# design.net
KiCad netlist of a schematic drawn in EasyEDA Pro
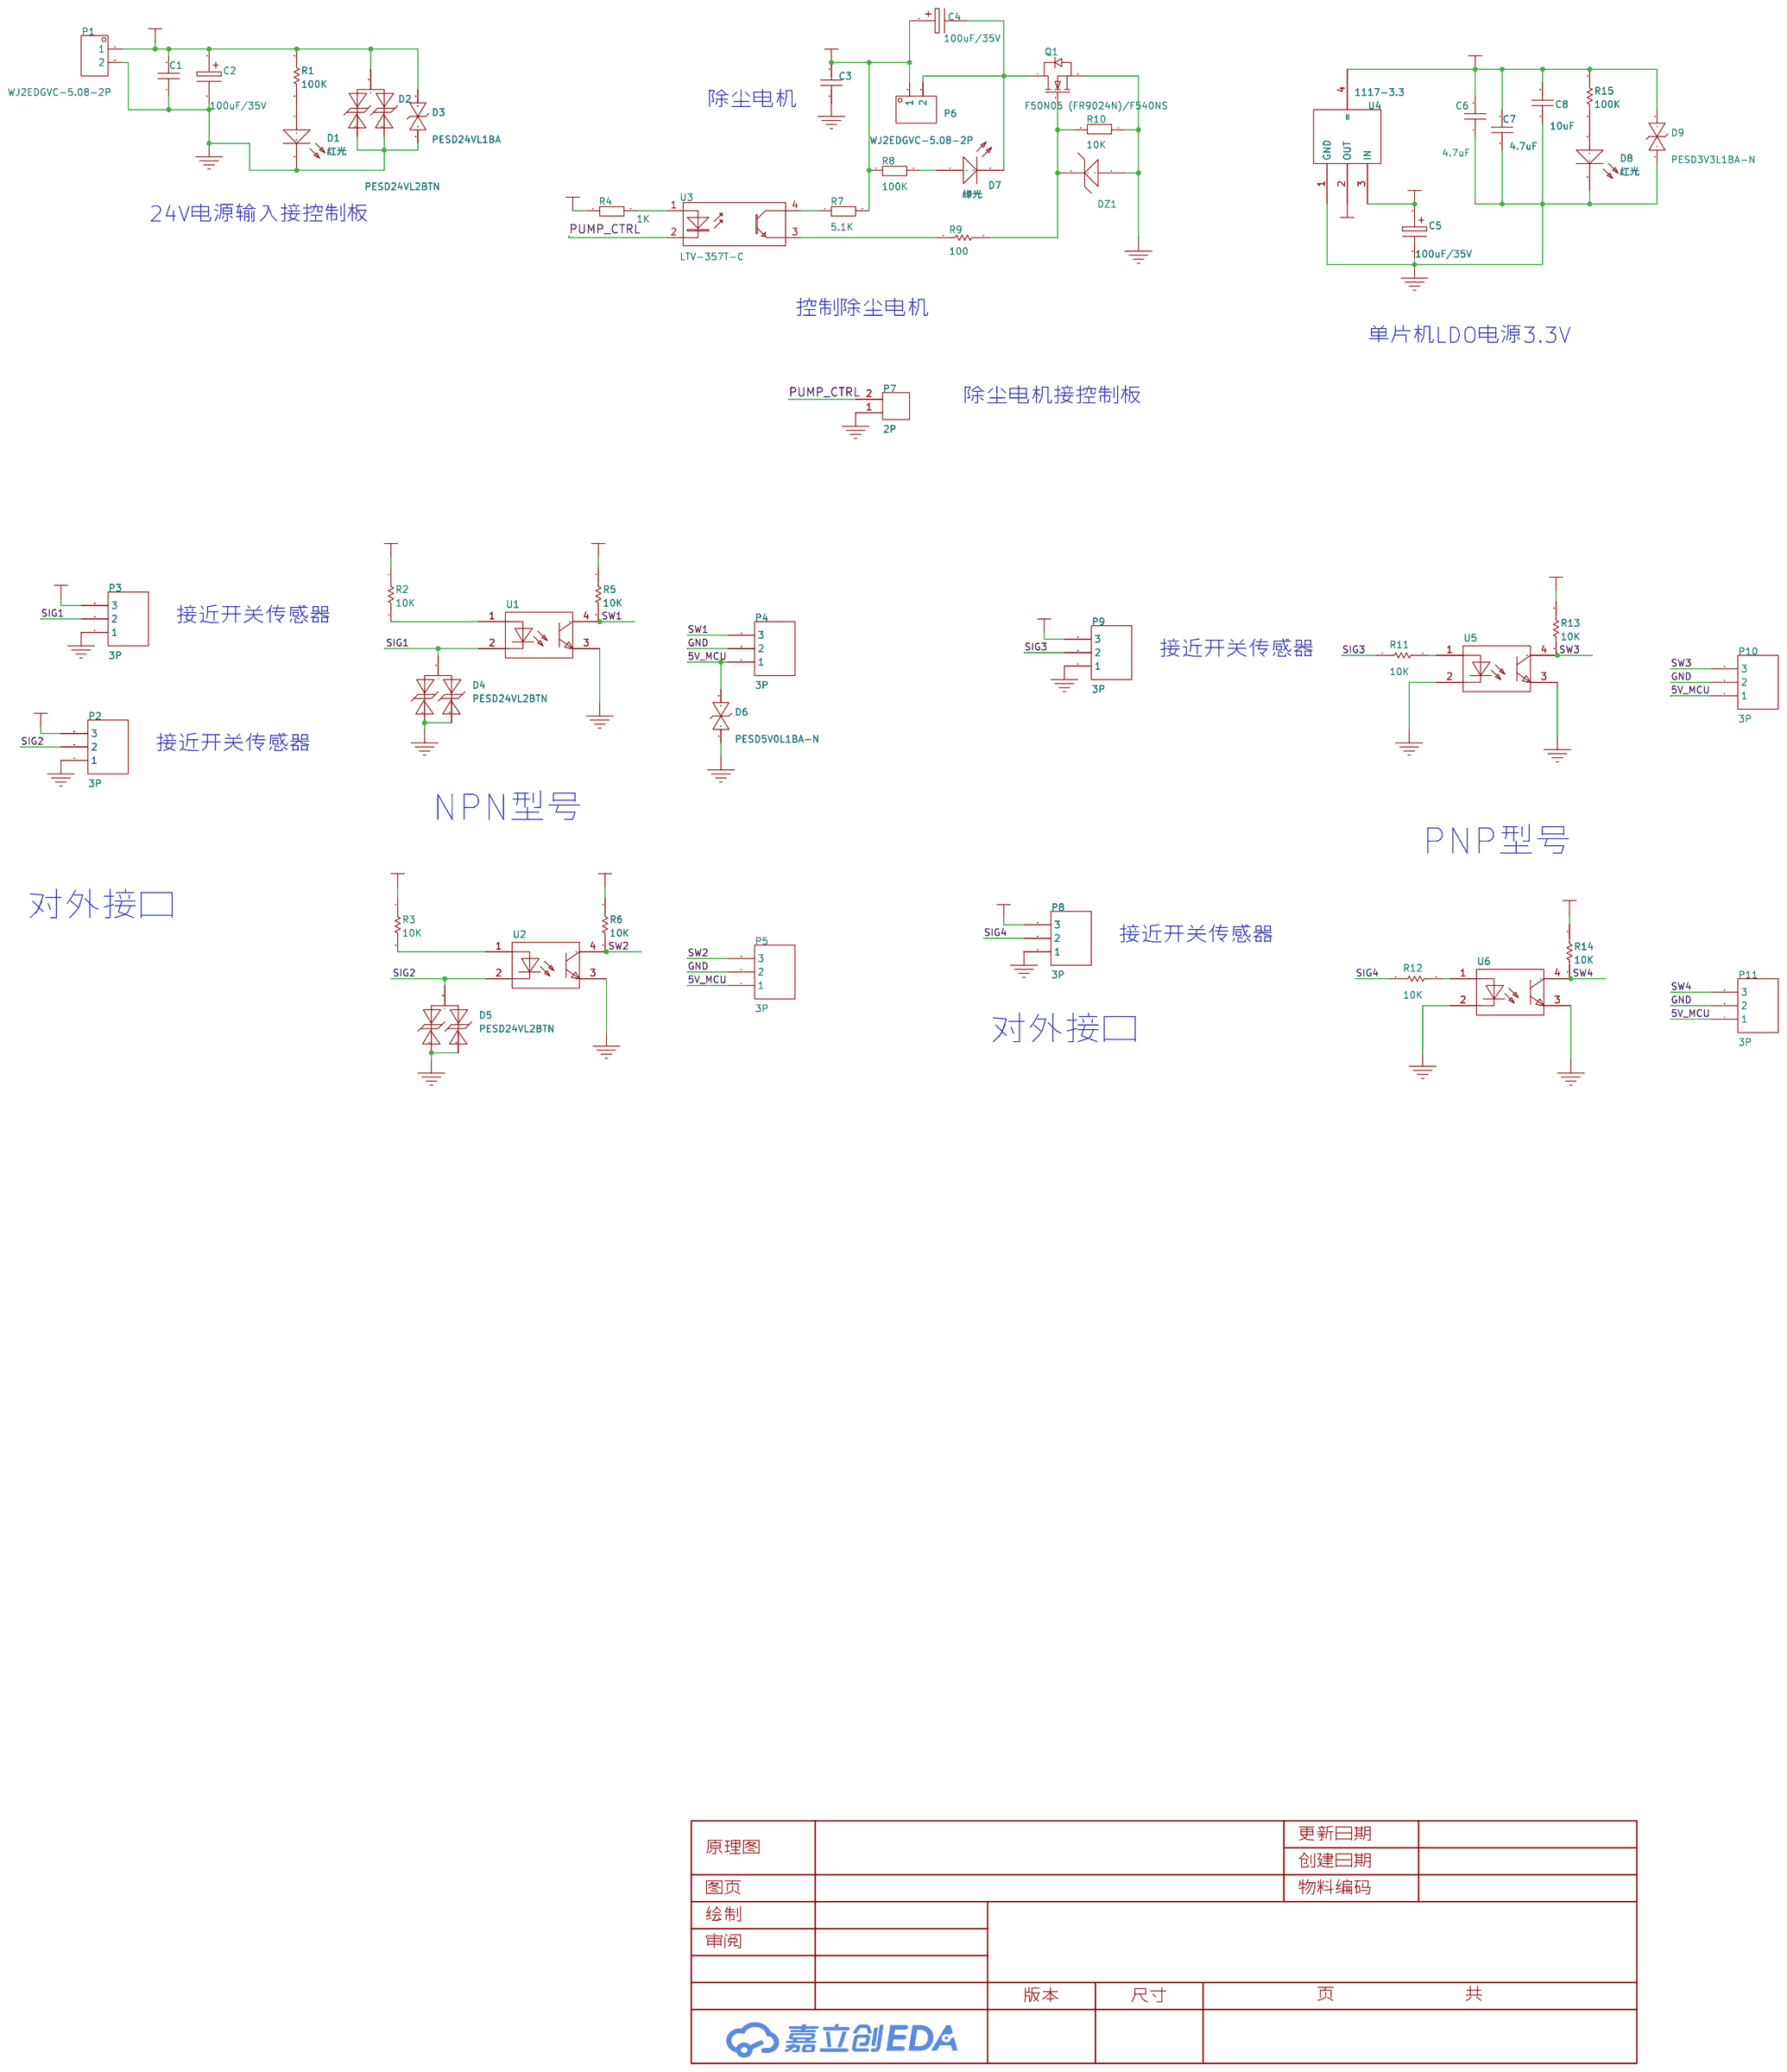
[diagram p0: 主控MCU]
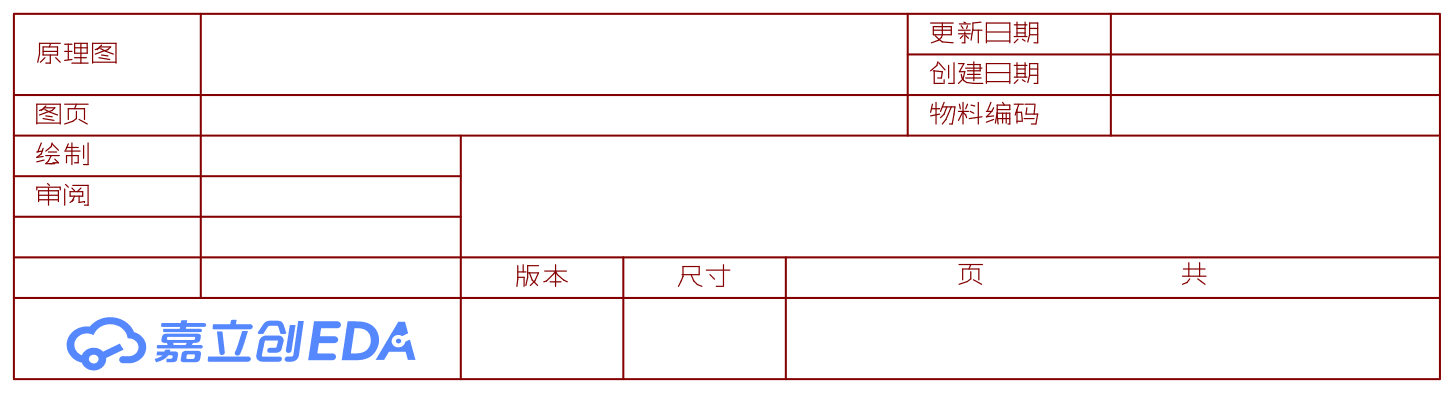
[diagram p1: 电源及控制]

(export (version "E")
  (design (tool "Eeschema 10.0.6"))
  (components
    (comp (ref "C1")
      (value "104")
      (footprint "easyedapro:电解电容贴片6x6")
      (libsource (lib "easyedapro") (part "CAP"))
    )
    (comp (ref "C2") (value "100uF/35V") (libsource (lib "") (part "ELECTRO1_1")))
    (comp (ref "C3")
      (value "104")
      (footprint "easyedapro:电解电容贴片6x6")
      (libsource (lib "easyedapro") (part "CAP"))
    )
    (comp (ref "C4")
      (value "100uF/35V")
      (footprint "easyedapro:0603C")
      (libsource (lib "easyedapro") (part "ELECTRO1"))
    )
    (comp (ref "C5")
      (value "100uF/35V")
      (footprint "easyedapro:电解电容贴片10x10")
      (libsource (lib "easyedapro") (part "ELECTRO1"))
    )
    (comp (ref "C6")
      (value "4.7uF")
      (footprint "easyedapro:C1206")
      (description "容值:4.7uF;精度:±10%;额定电压:50V;材质(温度系数):X7R;")
      (fields (field (name "Manufacturer Part") "1206B475K500NT") (field (name "Manufacturer") "FH(风华)"))
      (libsource (lib "easyedapro") (part "1206B475K500NT"))
    )
    (comp (ref "C7")
      (value "4.7uF")
      (footprint "easyedapro:C1206")
      (description "容值:4.7uF;精度:±10%;额定电压:50V;材质(温度系数):X7R;")
      (fields (field (name "Manufacturer Part") "1206B475K500NT") (field (name "Manufacturer") "FH(风华)"))
      (libsource (lib "easyedapro") (part "1206B475K500NT"))
    )
    (comp (ref "C8")
      (value "10uF")
      (footprint "easyedapro:0603C")
      (description "Capacitor (Semiconductor SIM Model)")
      (libsource (lib "easyedapro") (part "Cap Semi"))
    )
    (comp (ref "D1")
      (value "红光")
      (footprint "easyedapro:0603LED")
      (libsource (lib "easyedapro") (part "LED"))
    )
    (comp (ref "D2")
      (value "PESD24VL2BTN")
      (footprint "easyedapro:SOT-23-3_L2.9-W1.6-P1.90-LS2.8-BR")
      (description "极性:Bidirectional;反向关断电压（典型值）:24V (Max);击穿电压（最小值）:26.7V;箝位电压:48V;峰值脉冲电流（10/1000us）:6A (8/20us);")
      (fields (field (name "Manufacturer") "BORN伯恩半导体"))
      (libsource (lib "easyedapro") (part "PESD24VL2BTN"))
    )
    (comp (ref "D3")
      (value "PESD24VL1BA")
      (footprint "easyedapro:SOD-323_L1.7-W1.3-LS2.5-BI")
      (description "极性:双向;反向截止电压(Vrwm):3.3V;最大钳位电压:16V;击穿电压:4V;")
      (fields (field (name "Manufacturer") "TECH PUBLIC(台舟)"))
      (libsource (lib "easyedapro") (part "pesd03v32d-lc"))
    )
    (comp (ref "D4")
      (value "PESD24VL2BTN")
      (footprint "easyedapro:SOT-23-3_L2.9-W1.6-P1.90-LS2.8-BR")
      (description "极性:Bidirectional;反向关断电压（典型值）:24V (Max);击穿电压（最小值）:26.7V;箝位电压:48V;峰值脉冲电流（10/1000us）:6A (8/20us);")
      (fields (field (name "Manufacturer") "BORN伯恩半导体"))
      (libsource (lib "easyedapro") (part "PESD24VL2BTN"))
    )
    (comp (ref "D5")
      (value "PESD24VL2BTN")
      (footprint "easyedapro:SOT-23-3_L2.9-W1.6-P1.90-LS2.8-BR")
      (description "极性:Bidirectional;反向关断电压（典型值）:24V (Max);击穿电压（最小值）:26.7V;箝位电压:48V;峰值脉冲电流（10/1000us）:6A (8/20us);")
      (fields (field (name "Manufacturer") "BORN伯恩半导体"))
      (libsource (lib "easyedapro") (part "PESD24VL2BTN"))
    )
    (comp (ref "D6")
      (value "PESD5V0L1BA-N")
      (footprint "easyedapro:SOD-323_L1.7-W1.3-LS2.5-BI")
      (description "极性:双向;反向截止电压(Vrwm):3.3V;最大钳位电压:16V;击穿电压:4V;")
      (fields (field (name "Manufacturer") "TECH PUBLIC(台舟)"))
      (libsource (lib "easyedapro") (part "pesd03v32d-lc"))
    )
    (comp (ref "D7") (value "绿光") (footprint "easyedapro:SMA") (libsource (lib "easyedapro") (part "LED")))
    (comp (ref "D8")
      (value "红光")
      (footprint "easyedapro:0603LED")
      (libsource (lib "easyedapro") (part "LED"))
    )
    (comp (ref "D9")
      (value "PESD3V3L1BA-N")
      (footprint "easyedapro:SOD-323_L1.7-W1.3-LS2.5-BI")
      (description "极性:双向;反向截止电压(Vrwm):3.3V;最大钳位电压:16V;击穿电压:4V;")
      (fields (field (name "Manufacturer") "TECH PUBLIC(台舟)"))
      (libsource (lib "easyedapro") (part "pesd03v32d-lc"))
    )
    (comp (ref "DZ1") (value "--ѹ------SMAZ10V") (libsource (lib "easyedapro") (part "ѹ")))
    (comp (ref "P1")
      (value "WJ2EDGVC-5.08-2P")
      (footprint "easyedapro:CONN-TH_WJ2EDGVC-5.08-2P")
      (fields (field (name "Manufacturer") "KANGNEX(康奈克斯电气)"))
      (libsource (lib "easyedapro") (part "WJ2EDGVC-5.08-2P"))
    )
    (comp (ref "P2")
      (value "3P")
      (footprint "easyedapro:HDR1X3_CON")
      (libsource (lib "easyedapro") (part "3P"))
    )
    (comp (ref "P3")
      (value "3P")
      (footprint "easyedapro:HDR1X3_CON")
      (libsource (lib "easyedapro") (part "3P"))
    )
    (comp (ref "P4")
      (value "3P")
      (footprint "easyedapro:HDR1X3_CON")
      (libsource (lib "easyedapro") (part "3P"))
    )
    (comp (ref "P5")
      (value "3P")
      (footprint "easyedapro:HDR1X3_CON")
      (libsource (lib "easyedapro") (part "3P"))
    )
    (comp (ref "P6")
      (value "WJ2EDGVC-5.08-2P")
      (footprint "easyedapro:CONN-TH_WJ2EDGVC-5.08-2P")
      (fields (field (name "Manufacturer") "KANGNEX(康奈克斯电气)"))
      (libsource (lib "easyedapro") (part "WJ2EDGVC-5.08-2P"))
    )
    (comp (ref "P7") (value "2P") (libsource (lib "easyedapro") (part "2P")))
    (comp (ref "P8")
      (value "3P")
      (footprint "easyedapro:HDR1X3_CON")
      (libsource (lib "easyedapro") (part "3P"))
    )
    (comp (ref "P9")
      (value "3P")
      (footprint "easyedapro:HDR1X3_CON")
      (libsource (lib "easyedapro") (part "3P"))
    )
    (comp (ref "P10")
      (value "3P")
      (footprint "easyedapro:HDR1X3_CON")
      (libsource (lib "easyedapro") (part "3P"))
    )
    (comp (ref "P11")
      (value "3P")
      (footprint "easyedapro:HDR1X3_CON")
      (libsource (lib "easyedapro") (part "3P"))
    )
    (comp (ref "Q1")
      (value "F50N06 (FR9024N)/F540NS")
      (footprint "easyedapro:TO-263-2_L10.0-W9.1-P5.08-LS15.2-TL")
      (fields (field (name "Manufacturer") "Infineon(英飞凌)"))
      (libsource (lib "easyedapro") (part "IRF540NSTRLPBF"))
    )
    (comp (ref "R1")
      (value "100K")
      (footprint "easyedapro:0603R")
      (description "Resistor")
      (libsource (lib "easyedapro") (part "RES"))
    )
    (comp (ref "R2")
      (value "10K")
      (footprint "easyedapro:0603R")
      (description "Resistor")
      (libsource (lib "easyedapro") (part "RES"))
    )
    (comp (ref "R3")
      (value "10K")
      (footprint "easyedapro:0603R")
      (description "Resistor")
      (libsource (lib "easyedapro") (part "RES"))
    )
    (comp (ref "R4") (value "1K") (footprint "easyedapro:0603R") (libsource (lib "easyedapro") (part "res")))
    (comp (ref "R5")
      (value "10K")
      (footprint "easyedapro:0603R")
      (description "Resistor")
      (libsource (lib "easyedapro") (part "RES"))
    )
    (comp (ref "R6")
      (value "10K")
      (footprint "easyedapro:0603R")
      (description "Resistor")
      (libsource (lib "easyedapro") (part "RES"))
    )
    (comp (ref "R7")
      (value "5.1K")
      (footprint "easyedapro:0603R")
      (libsource (lib "easyedapro") (part "res"))
    )
    (comp (ref "R8")
      (value "100K")
      (footprint "easyedapro:0603R")
      (libsource (lib "easyedapro") (part "res"))
    )
    (comp (ref "R9")
      (value "100")
      (footprint "easyedapro:0603R")
      (description "Resistor")
      (libsource (lib "easyedapro") (part "RES"))
    )
    (comp (ref "R10")
      (value "10K")
      (footprint "easyedapro:0603R")
      (libsource (lib "easyedapro") (part "res"))
    )
    (comp (ref "R11")
      (value "10K")
      (footprint "easyedapro:0603R")
      (description "Resistor")
      (libsource (lib "easyedapro") (part "RES"))
    )
    (comp (ref "R12")
      (value "10K")
      (footprint "easyedapro:0603R")
      (description "Resistor")
      (libsource (lib "easyedapro") (part "RES"))
    )
    (comp (ref "R13")
      (value "10K")
      (footprint "easyedapro:0603R")
      (description "Resistor")
      (libsource (lib "easyedapro") (part "RES"))
    )
    (comp (ref "R14")
      (value "10K")
      (footprint "easyedapro:0603R")
      (description "Resistor")
      (libsource (lib "easyedapro") (part "RES"))
    )
    (comp (ref "R15")
      (value "100K")
      (footprint "easyedapro:0603R")
      (description "Resistor")
      (libsource (lib "easyedapro") (part "RES"))
    )
    (comp (ref "U1")
      (value "LTV-357T-C")
      (footprint "easyedapro:SOP-4_L4.4-W3.9-P2.54-LS7.0-TL")
      (fields (field (name "Manufacturer") "LITEON(光宝)"))
      (libsource (lib "easyedapro") (part "LTV-357T-C"))
    )
    (comp (ref "U2")
      (value "LTV-357T-C")
      (footprint "easyedapro:SOP-4_L4.4-W3.9-P2.54-LS7.0-TL")
      (fields (field (name "Manufacturer") "LITEON(光宝)"))
      (libsource (lib "easyedapro") (part "LTV-357T-C"))
    )
    (comp (ref "U3")
      (value "LTV-357T-C")
      (footprint "easyedapro:SOT-23-5")
      (description "4-Pin Phototransistor Optocoupler")
      (libsource (lib "easyedapro") (part "Optoisolator1"))
    )
    (comp (ref "U4")
      (value "1117-3.3")
      (footprint "easyedapro:SOT-223")
      (libsource (lib "easyedapro") (part "LM1117"))
    )
    (comp (ref "U5")
      (value "LTV-357T-C")
      (footprint "easyedapro:SOP-4_L4.4-W3.9-P2.54-LS7.0-TL")
      (fields (field (name "Manufacturer") "LITEON(光宝)"))
      (libsource (lib "easyedapro") (part "LTV-357T-C"))
    )
    (comp (ref "U6")
      (value "LTV-357T-C")
      (footprint "easyedapro:SOP-4_L4.4-W3.9-P2.54-LS7.0-TL")
      (fields (field (name "Manufacturer") "LITEON(光宝)"))
      (libsource (lib "easyedapro") (part "LTV-357T-C"))
    )
  )
  (nets
    (net (code "1") (name "3V3") (class "Default")
      (node (ref "C6") (pin "2") (pinfunction "2_2") (pintype "input"))
      (node (ref "C7") (pin "2") (pinfunction "2_2") (pintype "input"))
      (node (ref "C8") (pin "2") (pinfunction "2_2") (pintype "unspecified"))
      (node (ref "D9") (pin "2") (pinfunction "2_2") (pintype "unspecified"))
      (node (ref "R13") (pin "1") (pinfunction "1_1") (pintype "unspecified"))
      (node (ref "R14") (pin "1") (pinfunction "1_1") (pintype "unspecified"))
      (node (ref "R15") (pin "1") (pinfunction "1_1") (pintype "unspecified"))
      (node (ref "R4") (pin "1") (pintype "unspecified"))
      (node (ref "R5") (pin "1") (pinfunction "1_1") (pintype "unspecified"))
      (node (ref "R6") (pin "1") (pinfunction "1_1") (pintype "unspecified"))
      (node (ref "U4") (pin "2") (pinfunction "OUT_2") (pintype "unspecified"))
      (node (ref "U4") (pin "4") (pinfunction "=_4") (pintype "unspecified"))
    )
    (net (code "2") (name "5V_MCU") (class "Default")
      (node (ref "C5") (pin "1") (pintype "unspecified"))
      (node (ref "D6") (pin "2") (pinfunction "2_2") (pintype "unspecified"))
      (node (ref "P10") (pin "1") (pinfunction "1_1") (pintype "unspecified"))
      (node (ref "P11") (pin "1") (pinfunction "1_1") (pintype "unspecified"))
      (node (ref "P4") (pin "1") (pinfunction "1_1") (pintype "unspecified"))
      (node (ref "P5") (pin "1") (pinfunction "1_1") (pintype "unspecified"))
      (node (ref "U4") (pin "3") (pinfunction "IN_3") (pintype "unspecified"))
    )
    (net (code "3") (name "24V") (class "Default")
      (node (ref "C1") (pin "2") (pinfunction "2_2") (pintype "unspecified"))
      (node (ref "C2") (pin "1") (pintype "input"))
      (node (ref "C3") (pin "2") (pinfunction "2_2") (pintype "unspecified"))
      (node (ref "C4") (pin "1") (pintype "unspecified"))
      (node (ref "D2") (pin "3") (pinfunction "A_3") (pintype "input"))
      (node (ref "D3") (pin "2") (pinfunction "2_2") (pintype "unspecified"))
      (node (ref "P1") (pin "1") (pinfunction "1_1") (pintype "unspecified"))
      (node (ref "P2") (pin "3") (pinfunction "3_3") (pintype "unspecified"))
      (node (ref "P3") (pin "3") (pinfunction "3_3") (pintype "unspecified"))
      (node (ref "P6") (pin "1") (pinfunction "1_1") (pintype "unspecified"))
      (node (ref "P8") (pin "3") (pinfunction "3_3") (pintype "unspecified"))
      (node (ref "P9") (pin "3") (pinfunction "3_3") (pintype "unspecified"))
      (node (ref "R1") (pin "1") (pinfunction "1_1") (pintype "unspecified"))
      (node (ref "R2") (pin "1") (pinfunction "1_1") (pintype "unspecified"))
      (node (ref "R3") (pin "1") (pinfunction "1_1") (pintype "unspecified"))
      (node (ref "R7") (pin "2") (pintype "unspecified"))
      (node (ref "R8") (pin "1") (pintype "unspecified"))
    )
    (net (code "4") (name "GND") (class "Default")
      (node (ref "C1") (pin "1") (pinfunction "1_1") (pintype "unspecified"))
      (node (ref "C2") (pin "2") (pintype "input"))
      (node (ref "C3") (pin "1") (pinfunction "1_1") (pintype "unspecified"))
      (node (ref "C5") (pin "2") (pintype "unspecified"))
      (node (ref "C6") (pin "1") (pinfunction "1_1") (pintype "input"))
      (node (ref "C7") (pin "1") (pinfunction "1_1") (pintype "input"))
      (node (ref "C8") (pin "1") (pinfunction "1_1") (pintype "unspecified"))
      (node (ref "D1") (pin "2") (pinfunction "2_2") (pintype "unspecified"))
      (node (ref "D2") (pin "1") (pinfunction "K_1") (pintype "input"))
      (node (ref "D2") (pin "2") (pinfunction "K_2") (pintype "input"))
      (node (ref "D3") (pin "1") (pinfunction "1_1") (pintype "unspecified"))
      (node (ref "D4") (pin "1") (pinfunction "K_1") (pintype "input"))
      (node (ref "D4") (pin "2") (pinfunction "K_2") (pintype "input"))
      (node (ref "D5") (pin "1") (pinfunction "K_1") (pintype "input"))
      (node (ref "D5") (pin "2") (pinfunction "K_2") (pintype "input"))
      (node (ref "D6") (pin "1") (pinfunction "1_1") (pintype "unspecified"))
      (node (ref "D8") (pin "2") (pinfunction "2_2") (pintype "unspecified"))
      (node (ref "D9") (pin "1") (pinfunction "1_1") (pintype "unspecified"))
      (node (ref "DZ1") (pin "1") (pinfunction "1_1") (pintype "input"))
      (node (ref "P1") (pin "2") (pinfunction "2_2") (pintype "unspecified"))
      (node (ref "P10") (pin "2") (pinfunction "2_2") (pintype "unspecified"))
      (node (ref "P11") (pin "2") (pinfunction "2_2") (pintype "unspecified"))
      (node (ref "P2") (pin "1") (pinfunction "1_1") (pintype "unspecified"))
      (node (ref "P3") (pin "1") (pinfunction "1_1") (pintype "unspecified"))
      (node (ref "P4") (pin "2") (pinfunction "2_2") (pintype "unspecified"))
      (node (ref "P5") (pin "2") (pinfunction "2_2") (pintype "unspecified"))
      (node (ref "P7") (pin "1") (pintype "input"))
      (node (ref "P8") (pin "1") (pinfunction "1_1") (pintype "unspecified"))
      (node (ref "P9") (pin "1") (pinfunction "1_1") (pintype "unspecified"))
      (node (ref "Q1") (pin "3") (pinfunction "S_3") (pintype "input"))
      (node (ref "R10") (pin "1") (pintype "unspecified"))
      (node (ref "U1") (pin "3") (pinfunction "3_3") (pintype "unspecified"))
      (node (ref "U2") (pin "3") (pinfunction "3_3") (pintype "unspecified"))
      (node (ref "U4") (pin "1") (pinfunction "GND_1") (pintype "unspecified"))
      (node (ref "U5") (pin "2") (pinfunction "2_2") (pintype "unspecified"))
      (node (ref "U5") (pin "3") (pinfunction "3_3") (pintype "unspecified"))
      (node (ref "U6") (pin "2") (pinfunction "2_2") (pintype "unspecified"))
      (node (ref "U6") (pin "3") (pinfunction "3_3") (pintype "unspecified"))
    )
    (net (code "5") (name "Net-(D1-Pad1)") (class "Default")
      (node (ref "D1") (pin "1") (pinfunction "1_1") (pintype "unspecified"))
      (node (ref "R1") (pin "2") (pinfunction "2_2") (pintype "unspecified"))
    )
    (net (code "6") (name "Net-(D7-Pad1)") (class "Default")
      (node (ref "D7") (pin "1") (pinfunction "1_1") (pintype "unspecified"))
      (node (ref "R8") (pin "2") (pintype "unspecified"))
    )
    (net (code "7") (name "Net-(D8-Pad1)") (class "Default")
      (node (ref "D8") (pin "1") (pinfunction "1_1") (pintype "unspecified"))
      (node (ref "R15") (pin "2") (pinfunction "2_2") (pintype "unspecified"))
    )
    (net (code "8") (name "Net-(Q1-D)") (class "Default")
      (node (ref "C4") (pin "2") (pintype "unspecified"))
      (node (ref "D7") (pin "2") (pinfunction "2_2") (pintype "unspecified"))
      (node (ref "P6") (pin "2") (pinfunction "2_2") (pintype "unspecified"))
      (node (ref "Q1") (pin "4") (pinfunction "D_4") (pintype "input"))
    )
    (net (code "9") (name "Net-(Q1-G)") (class "Default")
      (node (ref "DZ1") (pin "2") (pinfunction "2_2") (pintype "input"))
      (node (ref "Q1") (pin "1") (pinfunction "G_1") (pintype "input"))
      (node (ref "R10") (pin "2") (pintype "unspecified"))
      (node (ref "R9") (pin "1") (pinfunction "1_1") (pintype "unspecified"))
    )
    (net (code "10") (name "Net-(R2-Pad2)") (class "Default")
      (node (ref "R2") (pin "2") (pinfunction "2_2") (pintype "unspecified"))
      (node (ref "U1") (pin "1") (pinfunction "1_1") (pintype "unspecified"))
    )
    (net (code "11") (name "Net-(R3-Pad2)") (class "Default")
      (node (ref "R3") (pin "2") (pinfunction "2_2") (pintype "unspecified"))
      (node (ref "U2") (pin "1") (pinfunction "1_1") (pintype "unspecified"))
    )
    (net (code "12") (name "Net-(R11-Pad2)") (class "Default")
      (node (ref "R11") (pin "2") (pinfunction "2_2") (pintype "unspecified"))
      (node (ref "U5") (pin "1") (pinfunction "1_1") (pintype "unspecified"))
    )
    (net (code "13") (name "Net-(R12-Pad2)") (class "Default")
      (node (ref "R12") (pin "2") (pinfunction "2_2") (pintype "unspecified"))
      (node (ref "U6") (pin "1") (pinfunction "1_1") (pintype "unspecified"))
    )
    (net (code "14") (name "Net-(U3-A)") (class "Default")
      (node (ref "R4") (pin "2") (pintype "unspecified"))
      (node (ref "U3") (pin "1") (pinfunction "A_1") (pintype "unspecified"))
    )
    (net (code "15") (name "Net-(U3-C)") (class "Default")
      (node (ref "R7") (pin "1") (pintype "unspecified"))
      (node (ref "U3") (pin "4") (pinfunction "C_4") (pintype "unspecified"))
    )
    (net (code "16") (name "Net-(U3-E)") (class "Default")
      (node (ref "R9") (pin "2") (pinfunction "2_2") (pintype "unspecified"))
      (node (ref "U3") (pin "3") (pinfunction "E_3") (pintype "unspecified"))
    )
    (net (code "17") (name "PUMP_CTRL") (class "Default")
      (node (ref "P7") (pin "2") (pintype "input"))
      (node (ref "U3") (pin "2") (pinfunction "K_2") (pintype "unspecified"))
    )
    (net (code "18") (name "SIG1") (class "Default")
      (node (ref "D4") (pin "3") (pinfunction "A_3") (pintype "input"))
      (node (ref "P3") (pin "2") (pinfunction "2_2") (pintype "unspecified"))
      (node (ref "U1") (pin "2") (pinfunction "2_2") (pintype "unspecified"))
    )
    (net (code "19") (name "SIG2") (class "Default")
      (node (ref "D5") (pin "3") (pinfunction "A_3") (pintype "input"))
      (node (ref "P2") (pin "2") (pinfunction "2_2") (pintype "unspecified"))
      (node (ref "U2") (pin "2") (pinfunction "2_2") (pintype "unspecified"))
    )
    (net (code "20") (name "SIG3") (class "Default")
      (node (ref "P9") (pin "2") (pinfunction "2_2") (pintype "unspecified"))
      (node (ref "R11") (pin "1") (pinfunction "1_1") (pintype "unspecified"))
    )
    (net (code "21") (name "SIG4") (class "Default")
      (node (ref "P8") (pin "2") (pinfunction "2_2") (pintype "unspecified"))
      (node (ref "R12") (pin "1") (pinfunction "1_1") (pintype "unspecified"))
    )
    (net (code "22") (name "SW1") (class "Default")
      (node (ref "P4") (pin "3") (pinfunction "3_3") (pintype "unspecified"))
      (node (ref "R5") (pin "2") (pinfunction "2_2") (pintype "unspecified"))
      (node (ref "U1") (pin "4") (pinfunction "4_4") (pintype "unspecified"))
    )
    (net (code "23") (name "SW2") (class "Default")
      (node (ref "P5") (pin "3") (pinfunction "3_3") (pintype "unspecified"))
      (node (ref "R6") (pin "2") (pinfunction "2_2") (pintype "unspecified"))
      (node (ref "U2") (pin "4") (pinfunction "4_4") (pintype "unspecified"))
    )
    (net (code "24") (name "SW3") (class "Default")
      (node (ref "P10") (pin "3") (pinfunction "3_3") (pintype "unspecified"))
      (node (ref "R13") (pin "2") (pinfunction "2_2") (pintype "unspecified"))
      (node (ref "U5") (pin "4") (pinfunction "4_4") (pintype "unspecified"))
    )
    (net (code "25") (name "SW4") (class "Default")
      (node (ref "P11") (pin "3") (pinfunction "3_3") (pintype "unspecified"))
      (node (ref "R14") (pin "2") (pinfunction "2_2") (pintype "unspecified"))
      (node (ref "U6") (pin "4") (pinfunction "4_4") (pintype "unspecified"))
    )
  )
)
